# 02-Power_5v0.net
KiCad netlist of a schematic drawn in Altium Designer
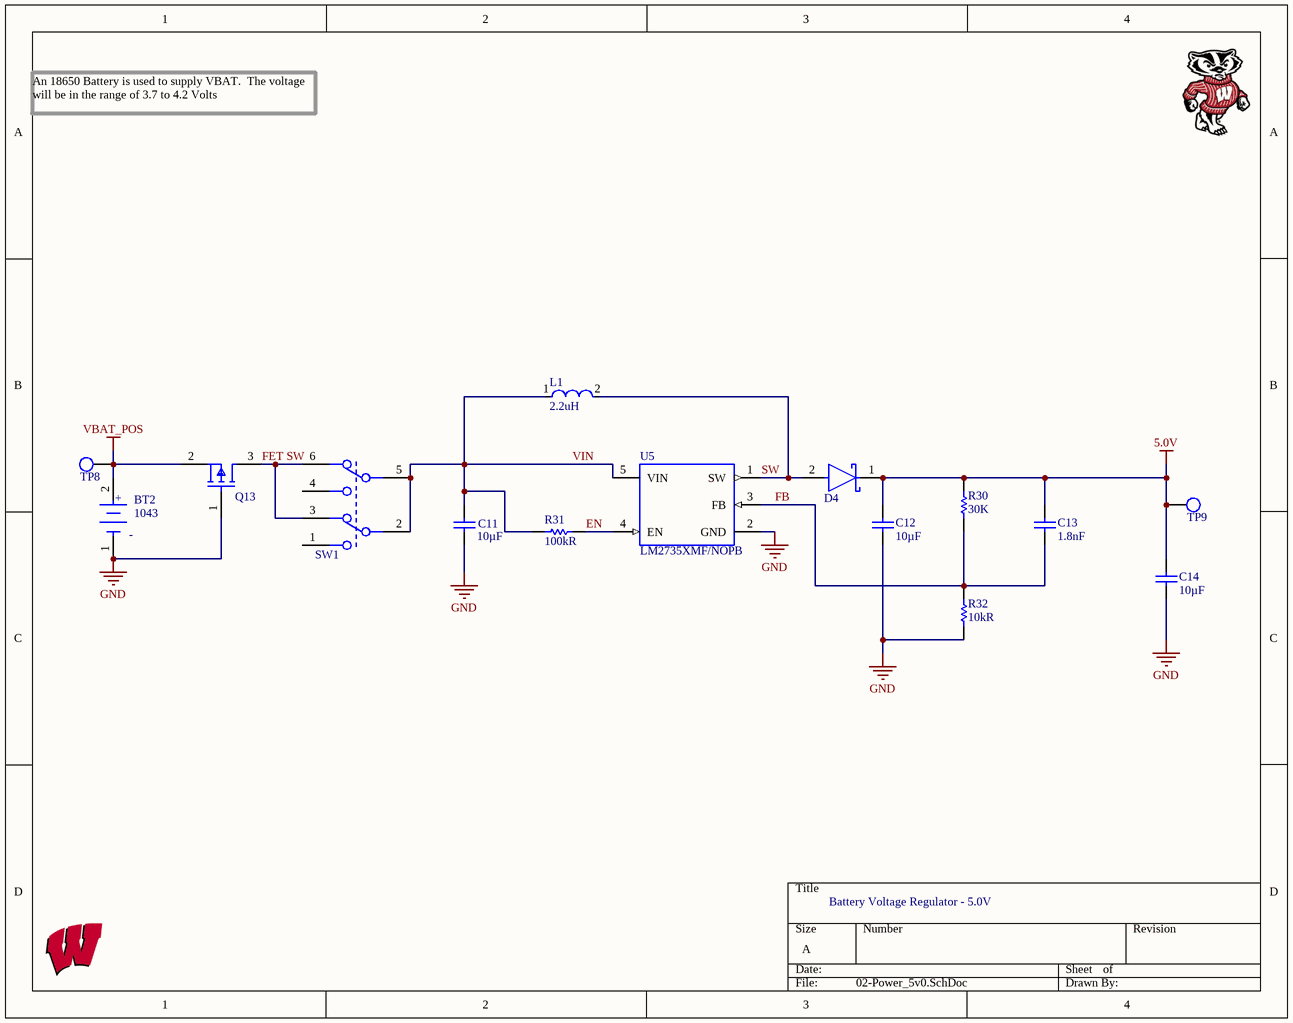
[diagram p0: 02-Power_5v0.SchDoc]

(export (version "E")
  (design (tool "Eeschema 10.0.6"))
  (components
    (comp (ref "BT2")
      (value "1043")
      (footprint "Keystone_1043_0")
      (description "Cylindrical Battery Contacts, Clips, Holders & Springs 18650 PCB PLASTIC BATT HLDR THM 1 CELL")
      (fields (field (name "MANUFACTURER PART NUMBER 1") "1043"))
      (libsource (lib "Battery") (part "1043"))
    )
    (comp (ref "C11")
      (value "10µF")
      (footprint "CAP_0805")
      (description "CAP CER 10UF 10V X5R 0805")
      (fields
        (field (name "MANUFACTURER") "Samsung Electro-Mechanics America, Inc.")
        (field (name "MANUFACTURER PART NUMBER") "CL21A106KPCLQNC")
      )
      (libsource (lib "Cap_Ceramic") (part "CAP_0805_U_010_00"))
    )
    (comp (ref "C12")
      (value "10µF")
      (footprint "CAP_0805")
      (description "CAP CER 10UF 10V X5R 0805")
      (fields
        (field (name "MANUFACTURER") "Samsung Electro-Mechanics America, Inc.")
        (field (name "MANUFACTURER PART NUMBER") "CL21A106KPCLQNC")
      )
      (libsource (lib "Cap_Ceramic") (part "CAP_0805_U_010_00"))
    )
    (comp (ref "C13")
      (value "CAP_0805_N_001_80")
      (footprint "CAP_0805")
      (fields
        (field (name "TOLERANCE") "5%")
        (field (name "VOLTAGE") "50V")
        (field (name "CAPACITANCE") "1.8nF")
      )
      (libsource (lib "Cap_Ceramic") (part "CAP_0805_N_001_80"))
    )
    (comp (ref "C14")
      (value "10µF")
      (footprint "CAP_0805")
      (description "CAP CER 10UF 10V X5R 0805")
      (fields
        (field (name "MANUFACTURER") "Samsung Electro-Mechanics America, Inc.")
        (field (name "MANUFACTURER PART NUMBER") "CL21A106KPCLQNC")
      )
      (libsource (lib "Cap_Ceramic") (part "CAP_0805_U_010_00"))
    )
    (comp (ref "D4")
      (value "SM5817PL-TP")
      (footprint "On_Semiconductor_425-04_IPC_A")
      (description "DIODE SCHOTTKY 20V 1A SOD123FL")
      (libsource (lib "Diodes") (part "SM5817PL-TP"))
    )
    (comp (ref "L1")
      (value "NRS4018T2R2MDGJ")
      (footprint "IND_TAIYO_NRS4018_TAY")
      (description "Inductor Power Shielded Wirewound 2.2uH 20% 100KHz Ferrite 2.2A 0.0504Ohm DCR 1515 T/R")
      (fields (field (name "TOLERANCE") "20%") (field (name "INDUCTANCE") "2.2uH"))
      (libsource (lib "Inductors") (part "NRS4018T2R2MDGJ"))
    )
    (comp (ref "Q13")
      (value "SSM3J328R,LF")
      (footprint "SOT-23_M")
      (description "MOSFET P-CH 20V 6A SOT23F")
      (libsource (lib "Transistors") (part "SSM3J328R,LF"))
    )
    (comp (ref "R30")
      (value "30K")
      (footprint "RES_0805")
      (description "Res Thick Film 0805 30K Ohm 1% 0.125W(1/8W) ±100ppm/°C Pad SMD Automotive T/R")
      (fields (field (name "TOLERANCE") "1%") (field (name "RESISTANCE") "30K"))
      (libsource (lib "Resistors") (part "RES_0805_K_030.00"))
    )
    (comp (ref "R31")
      (value "RES_0805_K_010.00")
      (footprint "RES_0805")
      (description "RES SMD 10K OHM 1% 1/8W 0805")
      (fields (field (name "TOLERANCE") "1%") (field (name "RESISTANCE") "100kR"))
      (libsource (lib "Resistors") (part "RES_0805_K_010.00"))
    )
    (comp (ref "R32")
      (value "RES_0805_K_010.00")
      (footprint "RES_0805")
      (description "RES SMD 10K OHM 1% 1/8W 0805")
      (fields (field (name "TOLERANCE") "1%") (field (name "RESISTANCE") "10kR"))
      (libsource (lib "Resistors") (part "RES_0805_K_010.00"))
    )
    (comp (ref "SW1")
      (value "JS202011SCQN")
      (footprint "C&K_Components_0_MFG")
      (description "C & K COMPONENTS - JS202011SCQN - SWITCH, DPDT, 0.6A, 6VDC, SMD")
      (libsource (lib "Switches") (part "JS202011SCQN"))
    )
    (comp (ref "TP8")
      (value "TP_1206")
      (footprint "TP-SMC-1206")
      (description "Test Point SMD 1206")
      (fields
        (field (name "MANUFACTURER") "TE Connectivity (Tyco Electronics)")
        (field (name "MANUFACTURER PART NUMBER") "1625854-1")
      )
      (libsource (lib "Mechanical") (part "TP_1206"))
    )
    (comp (ref "TP9")
      (value "TP_1206")
      (footprint "TP-SMC-1206")
      (description "Test Point SMD 1206")
      (fields
        (field (name "MANUFACTURER") "TE Connectivity (Tyco Electronics)")
        (field (name "MANUFACTURER PART NUMBER") "1625854-1")
      )
      (libsource (lib "Mechanical") (part "TP_1206"))
    )
    (comp (ref "U5")
      (value "LM2735XMF-NOPB")
      (footprint "Texas_Instruments_DBV0005A_0")
      (description "IC REG MULT CONFG ADJ 2.1A SOT23")
      (fields (field (name "MANUFACTURER PART NUMBER 1") "LM2735XMF/NOPB"))
      (libsource (lib "Regulators") (part "LM2735XMF-NOPB"))
    )
  )
  (nets
    (net (code "1") (name "/EN") (class "Default")
      (node (ref "R31") (pin "1") (pinfunction "1_1") (pintype "passive"))
      (node (ref "U5") (pin "4") (pinfunction "EN_4") (pintype "input"))
    )
    (net (code "2") (name "/FB") (class "Default")
      (node (ref "C13") (pin "1") (pinfunction "1_1") (pintype "passive"))
      (node (ref "R30") (pin "2") (pinfunction "2_2") (pintype "passive"))
      (node (ref "R32") (pin "2") (pinfunction "2_2") (pintype "passive"))
      (node (ref "U5") (pin "3") (pinfunction "FB_3") (pintype "input"))
    )
    (net (code "3") (name "/FET SW") (class "Default")
      (node (ref "Q13") (pin "3") (pinfunction "Drain_3") (pintype "passive"))
      (node (ref "SW1") (pin "3") (pinfunction "3_3") (pintype "passive"))
      (node (ref "SW1") (pin "6") (pinfunction "6_6") (pintype "passive"))
    )
    (net (code "4") (name "/SW") (class "Default")
      (node (ref "D4") (pin "2") (pinfunction "A_2") (pintype "passive"))
      (node (ref "L1") (pin "2") (pinfunction "2_2") (pintype "passive"))
      (node (ref "U5") (pin "1") (pinfunction "SW_1") (pintype "output"))
    )
    (net (code "5") (name "/VIN") (class "Default")
      (node (ref "C11") (pin "2") (pinfunction "2_2") (pintype "passive"))
      (node (ref "L1") (pin "1") (pinfunction "1_1") (pintype "passive"))
      (node (ref "R31") (pin "2") (pinfunction "2_2") (pintype "passive"))
      (node (ref "SW1") (pin "2") (pinfunction "2_2") (pintype "passive"))
      (node (ref "SW1") (pin "5") (pinfunction "5_5") (pintype "passive"))
      (node (ref "U5") (pin "5") (pinfunction "VIN_5") (pintype "power_in"))
    )
    (net (code "6") (name "5.0V") (class "Default")
      (node (ref "C12") (pin "2") (pinfunction "2_2") (pintype "passive"))
      (node (ref "C13") (pin "2") (pinfunction "2_2") (pintype "passive"))
      (node (ref "C14") (pin "2") (pinfunction "2_2") (pintype "passive"))
      (node (ref "D4") (pin "1") (pinfunction "C_1") (pintype "passive"))
      (node (ref "R30") (pin "1") (pinfunction "1_1") (pintype "passive"))
      (node (ref "TP9") (pin "1") (pintype "passive"))
    )
    (net (code "7") (name "GND") (class "Default")
      (node (ref "BT2") (pin "1") (pinfunction "C_1") (pintype "passive"))
      (node (ref "C11") (pin "1") (pinfunction "1_1") (pintype "passive"))
      (node (ref "C12") (pin "1") (pinfunction "1_1") (pintype "passive"))
      (node (ref "C14") (pin "1") (pinfunction "1_1") (pintype "passive"))
      (node (ref "Q13") (pin "1") (pinfunction "Gate_1") (pintype "passive"))
      (node (ref "R32") (pin "1") (pinfunction "1_1") (pintype "passive"))
      (node (ref "U5") (pin "2") (pinfunction "GND_2") (pintype "power_in"))
    )
    (net (code "8") (name "VBAT_POS") (class "Default")
      (node (ref "BT2") (pin "2") (pinfunction "A_2") (pintype "passive"))
      (node (ref "Q13") (pin "2") (pinfunction "Source_2") (pintype "passive"))
      (node (ref "TP8") (pin "1") (pintype "passive"))
    )
    (net (code "9") (name "unconnected-(SW1-Pad1)") (class "Default")
      (node (ref "SW1") (pin "1") (pinfunction "1_1") (pintype "passive"))
    )
    (net (code "10") (name "unconnected-(SW1-Pad4)") (class "Default")
      (node (ref "SW1") (pin "4") (pinfunction "4_4") (pintype "passive"))
    )
  )
)
